# VCO.net
KiCad netlist of a schematic drawn in Altium Designer
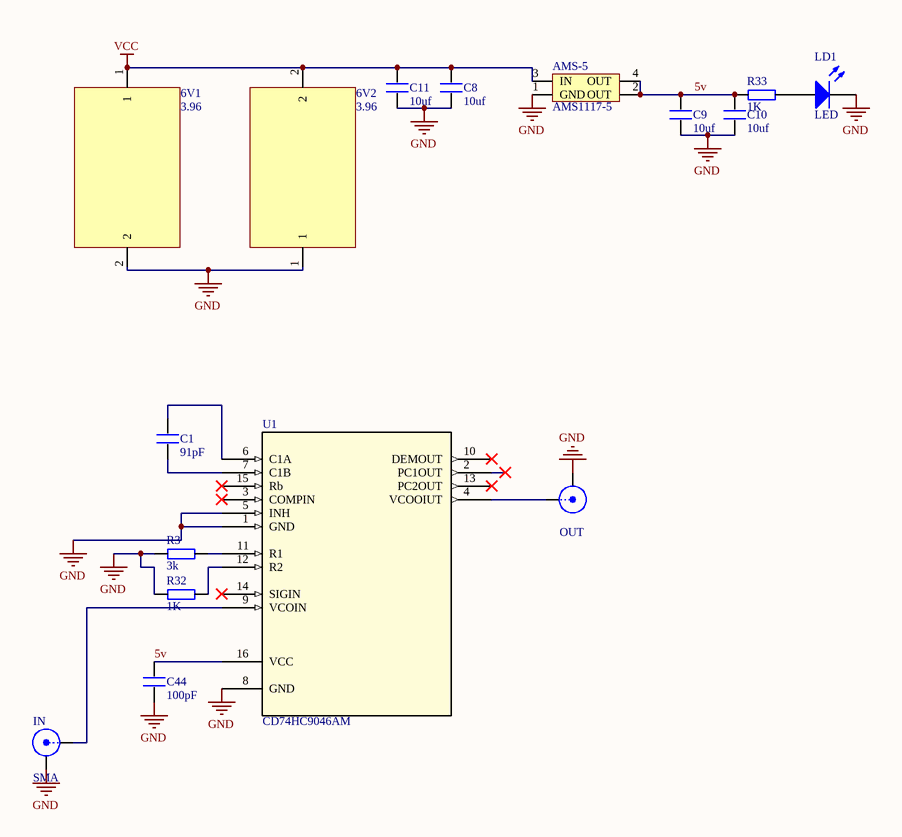
[diagram p0: VCO.SchDoc]

(export (version "E")
  (design (tool "Eeschema 10.0.6"))
  (components
    (comp (ref "6V1") (value "3.96") (footprint "3.96") (libsource (lib "") (part "3.96_1")))
    (comp (ref "6V2") (value "3.96") (footprint "3.96") (libsource (lib "MYLIB") (part "3.96")))
    (comp (ref "AMS-5") (value "AMS1117-5") (footprint "AMS1117") (libsource (lib "MYLIB") (part "AMS1117")))
    (comp (ref "C1")
      (value "91pF")
      (footprint "0603C")
      (description "Capacitor")
      (libsource (lib "MYLIB") (part "C"))
    )
    (comp (ref "C8")
      (value "10uf")
      (footprint "0603C")
      (description "Capacitor")
      (libsource (lib "MYLIB") (part "C"))
    )
    (comp (ref "C9")
      (value "10uf")
      (footprint "0603C")
      (description "Capacitor")
      (libsource (lib "MYLIB") (part "C"))
    )
    (comp (ref "C10")
      (value "10uf")
      (footprint "0603C")
      (description "Capacitor")
      (libsource (lib "MYLIB") (part "C"))
    )
    (comp (ref "C11")
      (value "10uf")
      (footprint "0603C")
      (description "Capacitor")
      (libsource (lib "MYLIB") (part "C"))
    )
    (comp (ref "C44")
      (value "100pF")
      (footprint "0603C")
      (description "Capacitor")
      (libsource (lib "MYLIB") (part "C"))
    )
    (comp (ref "IN")
      (value "SMA")
      (footprint "SMA")
      (description "SMA Connector")
      (libsource (lib "MYLIB") (part "SMA"))
    )
    (comp (ref "LD1")
      (value "LED")
      (footprint "SMDLED")
      (description "Typical RED, GREEN, YELLOW, AMBER GaAs LED")
      (fields (field (name "PUBLISHER") "Altium Limited"))
      (libsource (lib "MYLIB") (part "LED"))
    )
    (comp (ref "OUT")
      (value "SMA")
      (footprint "SMA")
      (description "SMA Connector")
      (libsource (lib "MYLIB") (part "SMA"))
    )
    (comp (ref "R3")
      (value "3k")
      (footprint "0603R")
      (description "Resistor")
      (libsource (lib "MYLIB") (part "Resistor"))
    )
    (comp (ref "R32")
      (value "1K")
      (footprint "0603R")
      (description "Resistor")
      (libsource (lib "MYLIB") (part "Resistor"))
    )
    (comp (ref "R33")
      (value "1K")
      (footprint "0603R")
      (description "Resistor")
      (libsource (lib "MYLIB") (part "Resistor"))
    )
    (comp (ref "U1")
      (value "CD74HC9046AM")
      (footprint "D16")
      (description "High Speed CMOS Logic Phase-Locked Loop with VCO and Lock Detector")
      (fields
        (field (name "MANUFACTURER") "Texas Instruments")
        (field (name "GENERIC_PART_NUMBER") "CD74HC7046A")
        (field (name "COPYRIGHT") "Copyright (C) 2018 Accelerated Designs. All rights reserved")
      )
      (libsource (lib "MYLIB") (part "CD74HC9046AM"))
    )
  )
  (nets
    (net (code "1") (name "/5v") (class "Default")
      (node (ref "AMS-5") (pin "2") (pinfunction "OUT_2") (pintype "passive"))
      (node (ref "AMS-5") (pin "4") (pinfunction "OUT_4") (pintype "passive"))
      (node (ref "C10") (pin "2") (pintype "passive"))
      (node (ref "C44") (pin "2") (pintype "passive"))
      (node (ref "C9") (pin "2") (pintype "passive"))
      (node (ref "R33") (pin "1") (pintype "passive"))
      (node (ref "U1") (pin "16") (pinfunction "VCC_16") (pintype "power_in"))
    )
    (net (code "2") (name "GND") (class "Default")
      (node (ref "6V1") (pin "2") (pinfunction "2_2") (pintype "passive"))
      (node (ref "6V2") (pin "1") (pinfunction "1_1") (pintype "passive"))
      (node (ref "AMS-5") (pin "1") (pinfunction "GND_1") (pintype "passive"))
      (node (ref "C10") (pin "1") (pintype "passive"))
      (node (ref "C11") (pin "1") (pintype "passive"))
      (node (ref "C44") (pin "1") (pintype "passive"))
      (node (ref "C8") (pin "1") (pintype "passive"))
      (node (ref "C9") (pin "1") (pintype "passive"))
      (node (ref "IN") (pin "2") (pinfunction "Y_2") (pintype "passive"))
      (node (ref "LD1") (pin "2") (pinfunction "K_2") (pintype "passive"))
      (node (ref "OUT") (pin "2") (pinfunction "Y_2") (pintype "passive"))
      (node (ref "R3") (pin "1") (pintype "passive"))
      (node (ref "R32") (pin "1") (pintype "passive"))
      (node (ref "U1") (pin "1") (pinfunction "GND_1") (pintype "input"))
      (node (ref "U1") (pin "5") (pinfunction "INH_5") (pintype "input"))
      (node (ref "U1") (pin "8") (pinfunction "GND_8") (pintype "power_in"))
    )
    (net (code "3") (name "Net-(IN-X)") (class "Default")
      (node (ref "IN") (pin "1") (pinfunction "X_1") (pintype "passive"))
      (node (ref "U1") (pin "9") (pinfunction "VCOIN_9") (pintype "input"))
    )
    (net (code "4") (name "Net-(LD1-A)") (class "Default")
      (node (ref "LD1") (pin "1") (pinfunction "A_1") (pintype "passive"))
      (node (ref "R33") (pin "2") (pintype "passive"))
    )
    (net (code "5") (name "Net-(OUT-X)") (class "Default")
      (node (ref "OUT") (pin "1") (pinfunction "X_1") (pintype "passive"))
      (node (ref "U1") (pin "4") (pinfunction "VCOOIUT_4") (pintype "output"))
    )
    (net (code "6") (name "Net-(U1-C1A)") (class "Default")
      (node (ref "C1") (pin "2") (pintype "passive"))
      (node (ref "U1") (pin "6") (pinfunction "C1A_6") (pintype "input"))
    )
    (net (code "7") (name "Net-(U1-C1B)") (class "Default")
      (node (ref "C1") (pin "1") (pintype "passive"))
      (node (ref "U1") (pin "7") (pinfunction "C1B_7") (pintype "input"))
    )
    (net (code "8") (name "Net-(U1-R1)") (class "Default")
      (node (ref "R3") (pin "2") (pintype "passive"))
      (node (ref "U1") (pin "11") (pinfunction "R1_11") (pintype "input"))
    )
    (net (code "9") (name "Net-(U1-R2)") (class "Default")
      (node (ref "R32") (pin "2") (pintype "passive"))
      (node (ref "U1") (pin "12") (pinfunction "R2_12") (pintype "input"))
    )
    (net (code "10") (name "VCC") (class "Default")
      (node (ref "6V1") (pin "1") (pinfunction "1_1") (pintype "passive"))
      (node (ref "6V2") (pin "2") (pinfunction "2_2") (pintype "passive"))
      (node (ref "AMS-5") (pin "3") (pinfunction "IN_3") (pintype "passive"))
      (node (ref "C11") (pin "2") (pintype "passive"))
      (node (ref "C8") (pin "2") (pintype "passive"))
    )
    (net (code "11") (name "unconnected-(U1-COMPIN-Pad3)") (class "Default")
      (node (ref "U1") (pin "3") (pinfunction "COMPIN_3") (pintype "input+no_connect"))
    )
    (net (code "12") (name "unconnected-(U1-DEMOUT-Pad10)") (class "Default")
      (node (ref "U1") (pin "10") (pinfunction "DEMOUT_10") (pintype "output+no_connect"))
    )
    (net (code "13") (name "unconnected-(U1-PC1OUT-Pad2)") (class "Default")
      (node (ref "U1") (pin "2") (pinfunction "PC1OUT_2") (pintype "output+no_connect"))
    )
    (net (code "14") (name "unconnected-(U1-PC2OUT-Pad13)") (class "Default")
      (node (ref "U1") (pin "13") (pinfunction "PC2OUT_13") (pintype "output+no_connect"))
    )
    (net (code "15") (name "unconnected-(U1-Rb-Pad15)") (class "Default")
      (node (ref "U1") (pin "15") (pinfunction "Rb_15") (pintype "input+no_connect"))
    )
    (net (code "16") (name "unconnected-(U1-SIGIN-Pad14)") (class "Default")
      (node (ref "U1") (pin "14") (pinfunction "SIGIN_14") (pintype "input+no_connect"))
    )
  )
)
